# STM32L.net
KiCad netlist of a schematic drawn in Altium Designer
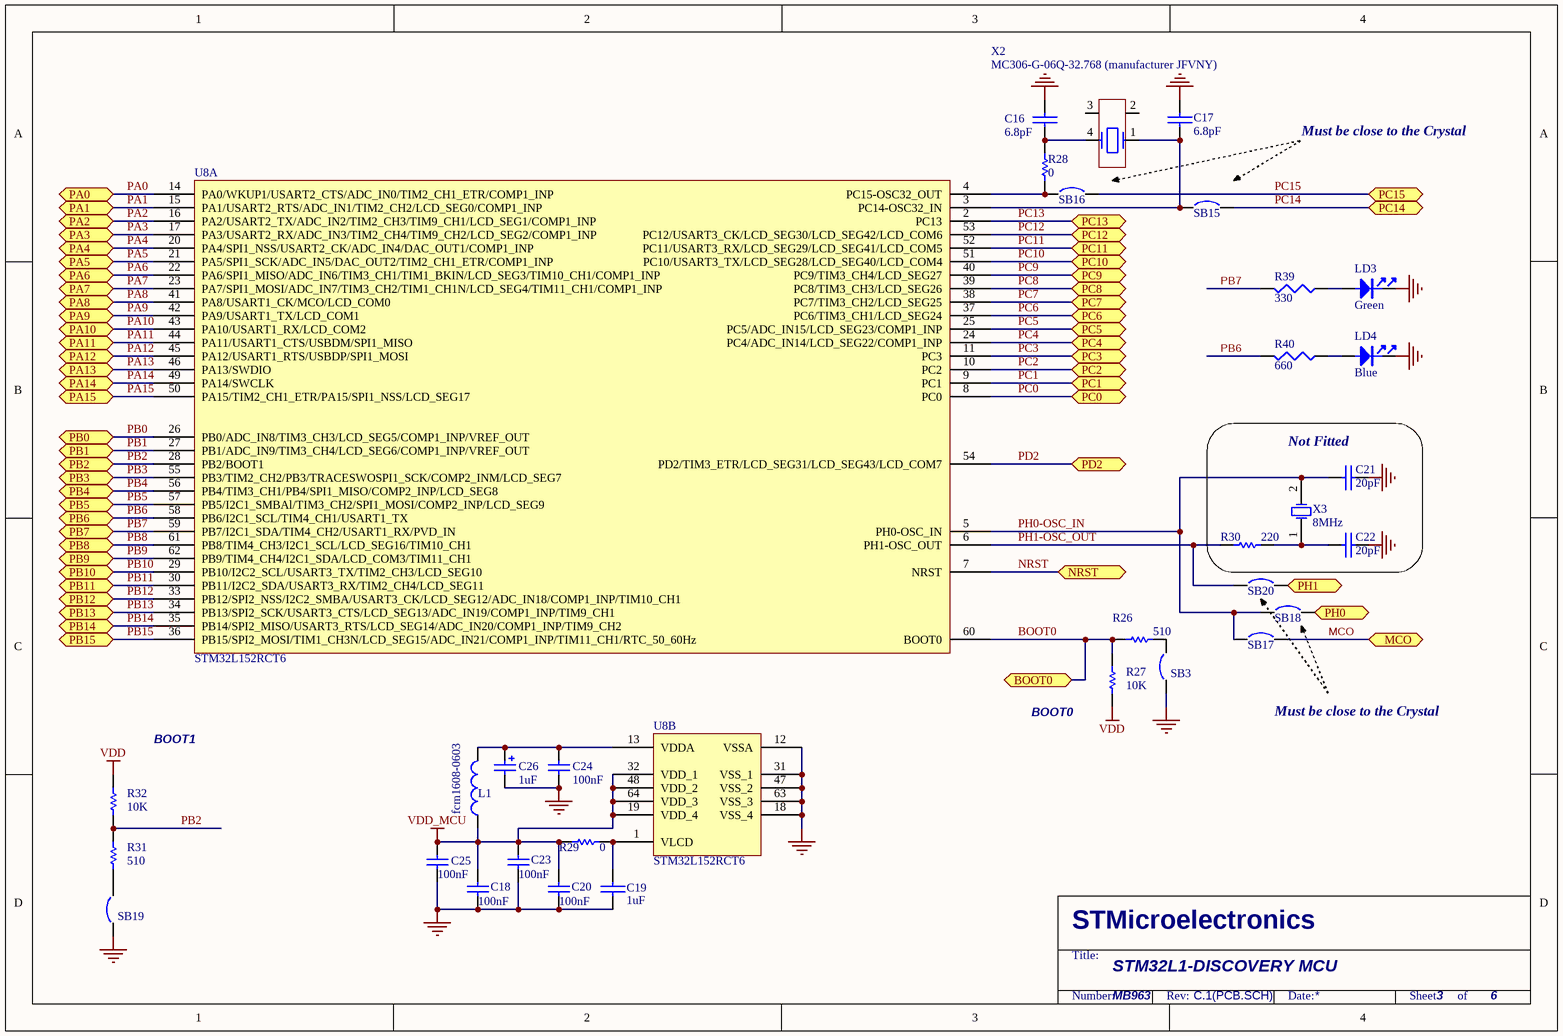
[diagram p0: STM32L.SchDoc]

(export (version "E")
  (design (tool "Eeschema 10.0.6"))
  (components
    (comp (ref "C16")
      (value "6.8pF")
      (footprint "0603C")
      (description "Capacitor")
      (libsource (lib "*") (part "CAP"))
    )
    (comp (ref "C17")
      (value "6.8pF")
      (footprint "0603C")
      (description "Capacitor")
      (libsource (lib "*") (part "CAP"))
    )
    (comp (ref "C18")
      (value "100nF")
      (footprint "0402C")
      (description "Capacitor")
      (fields (field (name "PUBLISHER") "Altium Limited"))
      (libsource (lib "MB915_1") (part "Cap"))
    )
    (comp (ref "C19")
      (value "1uF")
      (footprint "0603C")
      (description "Capacitor")
      (libsource (lib "") (part "CAP_1"))
    )
    (comp (ref "C20")
      (value "100nF")
      (footprint "0402C")
      (description "Capacitor")
      (fields (field (name "PUBLISHER") "Altium Limited"))
      (libsource (lib "MB915_1") (part "Cap"))
    )
    (comp (ref "C21")
      (value "20pF")
      (footprint "0603C")
      (description "Capacitor")
      (libsource (lib "") (part "CAP_1"))
    )
    (comp (ref "C22")
      (value "20pF")
      (footprint "0603C")
      (description "Capacitor")
      (libsource (lib "") (part "CAP_1"))
    )
    (comp (ref "C23")
      (value "100nF")
      (footprint "0402C")
      (description "Capacitor")
      (fields (field (name "PUBLISHER") "Altium Limited"))
      (libsource (lib "MB915_1") (part "Cap"))
    )
    (comp (ref "C24")
      (value "100nF")
      (footprint "0402C")
      (description "Capacitor")
      (fields (field (name "PUBLISHER") "Altium Limited"))
      (libsource (lib "MB915_1") (part "Cap"))
    )
    (comp (ref "C25")
      (value "100nF")
      (footprint "0402C")
      (description "Capacitor")
      (fields (field (name "PUBLISHER") "Altium Limited"))
      (libsource (lib "MB915_1") (part "Cap"))
    )
    (comp (ref "C26")
      (value "1uF")
      (footprint "CASE-AA")
      (description "Polarized Capacitor (Radial)")
      (fields (field (name "PUBLISHER") "Altium Limited"))
      (libsource (lib "Miscellaneous Devices") (part "Cap Pol1"))
    )
    (comp (ref "L1")
      (value "fcm1608-0603")
      (footprint "0603L")
      (description "Inductor")
      (fields (field (name "PUBLISHER") "Altium Limited"))
      (libsource (lib "Miscellaneous Devices") (part "Inductor"))
    )
    (comp (ref "LD3") (value "Green") (footprint "0603D") (libsource (lib "MB963_1") (part "PHOTO")))
    (comp (ref "LD4") (value "Blue") (footprint "0603D") (libsource (lib "MB963_1") (part "PHOTO")))
    (comp (ref "R26")
      (value "510")
      (footprint "0603R")
      (description "Resistor")
      (fields (field (name "PUBLISHER") "Altium Limited"))
      (libsource (lib "Miscellaneous Devices") (part "Res1"))
    )
    (comp (ref "R27")
      (value "10K")
      (footprint "0402R")
      (description "Resistor")
      (fields (field (name "PUBLISHER") "Altium Limited"))
      (libsource (lib "Miscellaneous Devices") (part "res1"))
    )
    (comp (ref "R28")
      (value "0")
      (footprint "0603R")
      (description "Resistor")
      (fields (field (name "PUBLISHER") "Altium Limited"))
      (libsource (lib "Miscellaneous Devices") (part "Res1"))
    )
    (comp (ref "R29")
      (value "0")
      (footprint "0402R")
      (description "Resistor")
      (fields (field (name "PUBLISHER") "Altium Limited"))
      (libsource (lib "Miscellaneous Devices") (part "res1"))
    )
    (comp (ref "R30")
      (value "220")
      (footprint "0603R")
      (description "Resistor")
      (fields (field (name "PUBLISHER") "Altium Limited"))
      (libsource (lib "Miscellaneous Devices") (part "Res1"))
    )
    (comp (ref "R31")
      (value "510")
      (footprint "0603R")
      (description "Resistor")
      (fields (field (name "PUBLISHER") "Altium Limited"))
      (libsource (lib "Miscellaneous Devices") (part "res1"))
    )
    (comp (ref "R32")
      (value "10K")
      (footprint "0402R")
      (description "Resistor")
      (fields (field (name "PUBLISHER") "Altium Limited"))
      (libsource (lib "Miscellaneous Devices") (part "res1"))
    )
    (comp (ref "R39") (value "330") (footprint "0603R") (libsource (lib "*") (part "RES1")))
    (comp (ref "R40") (value "660") (footprint "0603R") (libsource (lib "*") (part "RES1")))
    (comp (ref "SB3")
      (value "Circuit Breaker")
      (footprint "JP2_SMD")
      (fields (field (name "PUBLISHER") "Altium Limited"))
      (libsource (lib "MB915") (part "Circuit Breaker"))
    )
    (comp (ref "SB15")
      (value "Circuit Breaker")
      (footprint "JP2_SMD")
      (fields (field (name "PUBLISHER") "Altium Limited"))
      (libsource (lib "MB915") (part "Circuit Breaker"))
    )
    (comp (ref "SB16")
      (value "Circuit Breaker")
      (footprint "JP2_SMD")
      (fields (field (name "PUBLISHER") "Altium Limited"))
      (libsource (lib "MB915") (part "Circuit Breaker"))
    )
    (comp (ref "SB17")
      (value "Circuit Breaker")
      (footprint "JP2_SMD")
      (fields (field (name "PUBLISHER") "Altium Limited"))
      (libsource (lib "MB915") (part "Circuit Breaker"))
    )
    (comp (ref "SB18")
      (value "Circuit Breaker")
      (footprint "JP2_SMD")
      (fields (field (name "PUBLISHER") "Altium Limited"))
      (libsource (lib "MB915") (part "Circuit Breaker"))
    )
    (comp (ref "SB19")
      (value "Circuit Breaker")
      (footprint "JP2_SMD")
      (fields (field (name "PUBLISHER") "Altium Limited"))
      (libsource (lib "MB915") (part "Circuit Breaker"))
    )
    (comp (ref "SB20")
      (value "Circuit Breaker")
      (footprint "JP2_SMD")
      (fields (field (name "PUBLISHER") "Altium Limited"))
      (libsource (lib "MB915") (part "Circuit Breaker"))
    )
    (comp (ref "U8")
      (value "STM32L152RCT6")
      (footprint "QFP64")
      (description "32-bit 256K MCU (SCORPIO2 Shrink)")
      (libsource (lib "MB963") (part "STM32L152RCT6"))
    )
    (comp (ref "X2")
      (value "MC306-G-06Q-32.768 (manufacturer JFVNY)")
      (footprint "MC306-CRYSTAL")
      (libsource (lib "*") (part "MC306"))
    )
    (comp (ref "X3")
      (value "8MHz")
      (footprint "XTAL1")
      (description "Crystal Oscillator")
      (fields (field (name "PUBLISHER") "Altium Limited"))
      (libsource (lib "MB963_1") (part "XTAL"))
    )
  )
  (nets
    (net (code "1") (name "/BOOT0") (class "Default")
      (node (ref "R26") (pin "2") (pinfunction "2_2") (pintype "passive"))
      (node (ref "R27") (pin "1") (pinfunction "1_1") (pintype "passive"))
      (node (ref "U8") (pin "60") (pinfunction "BOOT0_60") (pintype "passive"))
    )
    (net (code "2") (name "/MCO") (class "Default")
      (node (ref "SB17") (pin "2") (pinfunction "2_2") (pintype "passive"))
    )
    (net (code "3") (name "/NRST") (class "Default")
      (node (ref "U8") (pin "7") (pinfunction "NRST_7") (pintype "passive"))
    )
    (net (code "4") (name "/PA0") (class "Default")
      (node (ref "U8") (pin "14") (pinfunction "PA0/WKUP1/USART2_CTS/ADC_IN0/TIM2_CH1_ETR/COMP1_INP_14") (pintype "passive"))
    )
    (net (code "5") (name "/PA1") (class "Default")
      (node (ref "U8") (pin "15") (pinfunction "PA1/USART2_RTS/ADC_IN1/TIM2_CH2/LCD_SEG0/COMP1_INP_15") (pintype "passive"))
    )
    (net (code "6") (name "/PA2") (class "Default")
      (node (ref "U8") (pin "16") (pinfunction "PA2/USART2_TX/ADC_IN2/TIM2_CH3/TIM9_CH1/LCD_SEG1/COMP1_INP_16") (pintype "passive"))
    )
    (net (code "7") (name "/PA3") (class "Default")
      (node (ref "U8") (pin "17") (pinfunction "PA3/USART2_RX/ADC_IN3/TIM2_CH4/TIM9_CH2/LCD_SEG2/COMP1_INP_17") (pintype "passive"))
    )
    (net (code "8") (name "/PA4") (class "Default")
      (node (ref "U8") (pin "20") (pinfunction "PA4/SPI1_NSS/USART2_CK/ADC_IN4/DAC_OUT1/COMP1_INP_20") (pintype "passive"))
    )
    (net (code "9") (name "/PA5") (class "Default")
      (node (ref "U8") (pin "21") (pinfunction "PA5/SPI1_SCK/ADC_IN5/DAC_OUT2/TIM2_CH1_ETR/COMP1_INP_21") (pintype "passive"))
    )
    (net (code "10") (name "/PA6") (class "Default")
      (node (ref "U8") (pin "22") (pinfunction "PA6/SPI1_MISO/ADC_IN6/TIM3_CH1/TIM1_BKIN/LCD_SEG3/TIM10_CH1/COMP1_INP_22") (pintype "passive"))
    )
    (net (code "11") (name "/PA7") (class "Default")
      (node (ref "U8") (pin "23") (pinfunction "PA7/SPI1_MOSI/ADC_IN7/TIM3_CH2/TIM1_CH1N/LCD_SEG4/TIM11_CH1/COMP1_INP_23") (pintype "passive"))
    )
    (net (code "12") (name "/PA8") (class "Default")
      (node (ref "U8") (pin "41") (pinfunction "PA8/USART1_CK/MCO/LCD_COM0_41") (pintype "passive"))
    )
    (net (code "13") (name "/PA9") (class "Default")
      (node (ref "U8") (pin "42") (pinfunction "PA9/USART1_TX/LCD_COM1_42") (pintype "passive"))
    )
    (net (code "14") (name "/PA10") (class "Default")
      (node (ref "U8") (pin "43") (pinfunction "PA10/USART1_RX/LCD_COM2_43") (pintype "passive"))
    )
    (net (code "15") (name "/PA11") (class "Default")
      (node (ref "U8") (pin "44") (pinfunction "PA11/USART1_CTS/USBDM/SPI1_MISO_44") (pintype "passive"))
    )
    (net (code "16") (name "/PA12") (class "Default")
      (node (ref "U8") (pin "45") (pinfunction "PA12/USART1_RTS/USBDP/SPI1_MOSI_45") (pintype "passive"))
    )
    (net (code "17") (name "/PA13") (class "Default")
      (node (ref "U8") (pin "46") (pinfunction "PA13/SWDIO_46") (pintype "passive"))
    )
    (net (code "18") (name "/PA14") (class "Default")
      (node (ref "U8") (pin "49") (pinfunction "PA14/SWCLK_49") (pintype "passive"))
    )
    (net (code "19") (name "/PA15") (class "Default")
      (node (ref "U8") (pin "50") (pinfunction "PA15/TIM2_CH1_ETR/PA15/SPI1_NSS/LCD_SEG17_50") (pintype "passive"))
    )
    (net (code "20") (name "/PB0") (class "Default")
      (node (ref "U8") (pin "26") (pinfunction "PB0/ADC_IN8/TIM3_CH3/LCD_SEG5/COMP1_INP/VREF_OUT_26") (pintype "passive"))
    )
    (net (code "21") (name "/PB1") (class "Default")
      (node (ref "U8") (pin "27") (pinfunction "PB1/ADC_IN9/TIM3_CH4/LCD_SEG6/COMP1_INP/VREF_OUT_27") (pintype "passive"))
    )
    (net (code "22") (name "/PB2") (class "Default")
      (node (ref "R31") (pin "1") (pinfunction "1_1") (pintype "passive"))
      (node (ref "R32") (pin "2") (pinfunction "2_2") (pintype "passive"))
      (node (ref "U8") (pin "28") (pinfunction "PB2/BOOT1_28") (pintype "passive"))
    )
    (net (code "23") (name "/PB3") (class "Default")
      (node (ref "U8") (pin "55") (pinfunction "PB3/TIM2_CH2/PB3/TRACESWOSPI1_SCK/COMP2_INM/LCD_SEG7_55") (pintype "passive"))
    )
    (net (code "24") (name "/PB4") (class "Default")
      (node (ref "U8") (pin "56") (pinfunction "PB4/TIM3_CH1/PB4/SPI1_MISO/COMP2_INP/LCD_SEG8_56") (pintype "passive"))
    )
    (net (code "25") (name "/PB5") (class "Default")
      (node (ref "U8") (pin "57") (pinfunction "PB5/I2C1_SMBAl/TIM3_CH2/SPI1_MOSI/COMP2_INP/LCD_SEG9_57") (pintype "passive"))
    )
    (net (code "26") (name "/PB6") (class "Default")
      (node (ref "R40") (pin "2") (pinfunction "2_2") (pintype "passive"))
      (node (ref "U8") (pin "58") (pinfunction "PB6/I2C1_SCL/TIM4_CH1/USART1_TX_58") (pintype "passive"))
    )
    (net (code "27") (name "/PB7") (class "Default")
      (node (ref "R39") (pin "2") (pinfunction "2_2") (pintype "passive"))
      (node (ref "U8") (pin "59") (pinfunction "PB7/I2C1_SDA/TIM4_CH2/USART1_RX/PVD_IN_59") (pintype "passive"))
    )
    (net (code "28") (name "/PB8") (class "Default")
      (node (ref "U8") (pin "61") (pinfunction "PB8/TIM4_CH3/I2C1_SCL/LCD_SEG16/TIM10_CH1_61") (pintype "passive"))
    )
    (net (code "29") (name "/PB9") (class "Default")
      (node (ref "U8") (pin "62") (pinfunction "PB9/TIM4_CH4/I2C1_SDA/LCD_COM3/TIM11_CH1_62") (pintype "passive"))
    )
    (net (code "30") (name "/PB10") (class "Default")
      (node (ref "U8") (pin "29") (pinfunction "PB10/I2C2_SCL/USART3_TX/TIM2_CH3/LCD_SEG10_29") (pintype "passive"))
    )
    (net (code "31") (name "/PB11") (class "Default")
      (node (ref "U8") (pin "30") (pinfunction "PB11/I2C2_SDA/USART3_RX/TIM2_CH4/LCD_SEG11_30") (pintype "passive"))
    )
    (net (code "32") (name "/PB12") (class "Default")
      (node (ref "U8") (pin "33") (pinfunction "PB12/SPI2_NSS/I2C2_SMBA/USART3_CK/LCD_SEG12/ADC_IN18/COMP1_INP/TIM10_CH1_33") (pintype "passive"))
    )
    (net (code "33") (name "/PB13") (class "Default")
      (node (ref "U8") (pin "34") (pinfunction "PB13/SPI2_SCK/USART3_CTS/LCD_SEG13/ADC_IN19/COMP1_INP/TIM9_CH1_34") (pintype "passive"))
    )
    (net (code "34") (name "/PB14") (class "Default")
      (node (ref "U8") (pin "35") (pinfunction "PB14/SPI2_MISO/USART3_RTS/LCD_SEG14/ADC_IN20/COMP1_INP/TIM9_CH2_35") (pintype "passive"))
    )
    (net (code "35") (name "/PB15") (class "Default")
      (node (ref "U8") (pin "36") (pinfunction "PB15/SPI2_MOSI/TIM1_CH3N/LCD_SEG15/ADC_IN21/COMP1_INP/TIM11_CH1/RTC_50_60Hz_36") (pintype "passive"))
    )
    (net (code "36") (name "/PC0") (class "Default")
      (node (ref "U8") (pin "8") (pinfunction "PC0_8") (pintype "passive"))
    )
    (net (code "37") (name "/PC1") (class "Default")
      (node (ref "U8") (pin "9") (pinfunction "PC1_9") (pintype "passive"))
    )
    (net (code "38") (name "/PC2") (class "Default")
      (node (ref "U8") (pin "10") (pinfunction "PC2_10") (pintype "passive"))
    )
    (net (code "39") (name "/PC3") (class "Default")
      (node (ref "U8") (pin "11") (pinfunction "PC3_11") (pintype "passive"))
    )
    (net (code "40") (name "/PC4") (class "Default")
      (node (ref "U8") (pin "24") (pinfunction "PC4/ADC_IN14/LCD_SEG22/COMP1_INP_24") (pintype "passive"))
    )
    (net (code "41") (name "/PC5") (class "Default")
      (node (ref "U8") (pin "25") (pinfunction "PC5/ADC_IN15/LCD_SEG23/COMP1_INP_25") (pintype "passive"))
    )
    (net (code "42") (name "/PC6") (class "Default")
      (node (ref "U8") (pin "37") (pinfunction "PC6/TIM3_CH1/LCD_SEG24_37") (pintype "passive"))
    )
    (net (code "43") (name "/PC7") (class "Default")
      (node (ref "U8") (pin "38") (pinfunction "PC7/TIM3_CH2/LCD_SEG25_38") (pintype "passive"))
    )
    (net (code "44") (name "/PC8") (class "Default")
      (node (ref "U8") (pin "39") (pinfunction "PC8/TIM3_CH3/LCD_SEG26_39") (pintype "passive"))
    )
    (net (code "45") (name "/PC9") (class "Default")
      (node (ref "U8") (pin "40") (pinfunction "PC9/TIM3_CH4/LCD_SEG27_40") (pintype "passive"))
    )
    (net (code "46") (name "/PC10") (class "Default")
      (node (ref "U8") (pin "51") (pinfunction "PC10/USART3_TX/LCD_SEG28/LCD_SEG40/LCD_COM4_51") (pintype "passive"))
    )
    (net (code "47") (name "/PC11") (class "Default")
      (node (ref "U8") (pin "52") (pinfunction "PC11/USART3_RX/LCD_SEG29/LCD_SEG41/LCD_COM5_52") (pintype "passive"))
    )
    (net (code "48") (name "/PC12") (class "Default")
      (node (ref "U8") (pin "53") (pinfunction "PC12/USART3_CK/LCD_SEG30/LCD_SEG42/LCD_COM6_53") (pintype "passive"))
    )
    (net (code "49") (name "/PC13") (class "Default")
      (node (ref "U8") (pin "2") (pinfunction "PC13_2") (pintype "passive"))
    )
    (net (code "50") (name "/PC14") (class "Default")
      (node (ref "SB15") (pin "2") (pinfunction "2_2") (pintype "passive"))
    )
    (net (code "51") (name "/PC15") (class "Default")
      (node (ref "SB16") (pin "2") (pinfunction "2_2") (pintype "passive"))
    )
    (net (code "52") (name "/PD2") (class "Default")
      (node (ref "U8") (pin "54") (pinfunction "PD2/TIM3_ETR/LCD_SEG31/LCD_SEG43/LCD_COM7_54") (pintype "passive"))
    )
    (net (code "53") (name "/PH0") (class "Default")
      (node (ref "SB18") (pin "2") (pinfunction "2_2") (pintype "passive"))
    )
    (net (code "54") (name "/PH0-OSC_IN") (class "Default")
      (node (ref "C21") (pin "2") (pinfunction "2_2") (pintype "passive"))
      (node (ref "SB17") (pin "1") (pinfunction "1_1") (pintype "passive"))
      (node (ref "SB18") (pin "1") (pinfunction "1_1") (pintype "passive"))
      (node (ref "U8") (pin "5") (pinfunction "PH0-OSC_IN_5") (pintype "passive"))
      (node (ref "X3") (pin "2") (pinfunction "OSC2_2") (pintype "passive"))
    )
    (net (code "55") (name "/PH1") (class "Default")
      (node (ref "SB20") (pin "2") (pinfunction "2_2") (pintype "passive"))
    )
    (net (code "56") (name "/PH1-OSC_OUT") (class "Default")
      (node (ref "R30") (pin "2") (pinfunction "2_2") (pintype "passive"))
      (node (ref "SB20") (pin "1") (pinfunction "1_1") (pintype "passive"))
      (node (ref "U8") (pin "6") (pinfunction "PH1-OSC_OUT_6") (pintype "passive"))
    )
    (net (code "57") (name "GND") (class "Default")
      (node (ref "C16") (pin "2") (pinfunction "2_2") (pintype "passive"))
      (node (ref "C17") (pin "2") (pinfunction "2_2") (pintype "passive"))
      (node (ref "C18") (pin "1") (pinfunction "1_1") (pintype "passive"))
      (node (ref "C19") (pin "2") (pinfunction "2_2") (pintype "passive"))
      (node (ref "C20") (pin "1") (pinfunction "1_1") (pintype "passive"))
      (node (ref "C21") (pin "1") (pinfunction "1_1") (pintype "passive"))
      (node (ref "C22") (pin "1") (pinfunction "1_1") (pintype "passive"))
      (node (ref "C23") (pin "2") (pinfunction "2_2") (pintype "passive"))
      (node (ref "C24") (pin "1") (pinfunction "1_1") (pintype "passive"))
      (node (ref "C25") (pin "1") (pinfunction "1_1") (pintype "passive"))
      (node (ref "C26") (pin "2") (pinfunction "2_2") (pintype "passive"))
      (node (ref "LD3") (pin "2") (pintype "passive"))
      (node (ref "LD4") (pin "2") (pintype "passive"))
      (node (ref "SB19") (pin "1") (pinfunction "1_1") (pintype "passive"))
      (node (ref "SB3") (pin "1") (pinfunction "1_1") (pintype "passive"))
      (node (ref "U8") (pin "12") (pinfunction "VSSA_12") (pintype "passive"))
      (node (ref "U8") (pin "18") (pinfunction "VSS_4_18") (pintype "passive"))
      (node (ref "U8") (pin "31") (pinfunction "VSS_1_31") (pintype "passive"))
      (node (ref "U8") (pin "47") (pinfunction "VSS_2_47") (pintype "passive"))
      (node (ref "U8") (pin "63") (pinfunction "VSS_3_63") (pintype "passive"))
    )
    (net (code "58") (name "Net-(C16-Pad1)") (class "Default")
      (node (ref "C16") (pin "1") (pinfunction "1_1") (pintype "passive"))
      (node (ref "R28") (pin "1") (pinfunction "1_1") (pintype "passive"))
      (node (ref "X2") (pin "4") (pinfunction "4_4") (pintype "passive"))
    )
    (net (code "59") (name "Net-(LD3-Pad1)") (class "Default")
      (node (ref "LD3") (pin "1") (pintype "passive"))
      (node (ref "R39") (pin "1") (pinfunction "1_1") (pintype "passive"))
    )
    (net (code "60") (name "Net-(LD4-Pad1)") (class "Default")
      (node (ref "LD4") (pin "1") (pintype "passive"))
      (node (ref "R40") (pin "1") (pinfunction "1_1") (pintype "passive"))
    )
    (net (code "61") (name "Net-(R26-Pad1)") (class "Default")
      (node (ref "R26") (pin "1") (pinfunction "1_1") (pintype "passive"))
      (node (ref "SB3") (pin "2") (pinfunction "2_2") (pintype "passive"))
    )
    (net (code "62") (name "Net-(R31-Pad2)") (class "Default")
      (node (ref "R31") (pin "2") (pinfunction "2_2") (pintype "passive"))
      (node (ref "SB19") (pin "2") (pinfunction "2_2") (pintype "passive"))
    )
    (net (code "63") (name "Net-(U8A-PC14-OSC32_IN)") (class "Default")
      (node (ref "C17") (pin "1") (pinfunction "1_1") (pintype "passive"))
      (node (ref "SB15") (pin "1") (pinfunction "1_1") (pintype "passive"))
      (node (ref "U8") (pin "3") (pinfunction "PC14-OSC32_IN_3") (pintype "passive"))
      (node (ref "X2") (pin "1") (pinfunction "1_1") (pintype "passive"))
    )
    (net (code "64") (name "Net-(U8A-PC15-OSC32_OUT)") (class "Default")
      (node (ref "R28") (pin "2") (pinfunction "2_2") (pintype "passive"))
      (node (ref "SB16") (pin "1") (pinfunction "1_1") (pintype "passive"))
      (node (ref "U8") (pin "4") (pinfunction "PC15-OSC32_OUT_4") (pintype "passive"))
    )
    (net (code "65") (name "Net-(U8B-VDDA)") (class "Default")
      (node (ref "C24") (pin "2") (pinfunction "2_2") (pintype "passive"))
      (node (ref "C26") (pin "1") (pinfunction "1_1") (pintype "passive"))
      (node (ref "L1") (pin "2") (pinfunction "2_2") (pintype "passive"))
      (node (ref "U8") (pin "13") (pinfunction "VDDA_13") (pintype "passive"))
    )
    (net (code "66") (name "Net-(U8B-VLCD)") (class "Default")
      (node (ref "C19") (pin "1") (pinfunction "1_1") (pintype "passive"))
      (node (ref "R29") (pin "2") (pinfunction "2_2") (pintype "passive"))
      (node (ref "U8") (pin "1") (pinfunction "VLCD_1") (pintype "passive"))
    )
    (net (code "67") (name "Net-(X3-OSC1)") (class "Default")
      (node (ref "C22") (pin "2") (pinfunction "2_2") (pintype "passive"))
      (node (ref "R30") (pin "1") (pinfunction "1_1") (pintype "passive"))
      (node (ref "X3") (pin "1") (pinfunction "OSC1_1") (pintype "passive"))
    )
    (net (code "68") (name "VDD") (class "Default")
      (node (ref "R27") (pin "2") (pinfunction "2_2") (pintype "passive"))
      (node (ref "R32") (pin "1") (pinfunction "1_1") (pintype "passive"))
    )
    (net (code "69") (name "VDD_MCU") (class "Default")
      (node (ref "C18") (pin "2") (pinfunction "2_2") (pintype "passive"))
      (node (ref "C20") (pin "2") (pinfunction "2_2") (pintype "passive"))
      (node (ref "C23") (pin "1") (pinfunction "1_1") (pintype "passive"))
      (node (ref "C25") (pin "2") (pinfunction "2_2") (pintype "passive"))
      (node (ref "L1") (pin "1") (pinfunction "1_1") (pintype "passive"))
      (node (ref "R29") (pin "1") (pinfunction "1_1") (pintype "passive"))
      (node (ref "U8") (pin "19") (pinfunction "VDD_4_19") (pintype "passive"))
      (node (ref "U8") (pin "32") (pinfunction "VDD_1_32") (pintype "passive"))
      (node (ref "U8") (pin "48") (pinfunction "VDD_2_48") (pintype "passive"))
      (node (ref "U8") (pin "64") (pinfunction "VDD_3_64") (pintype "passive"))
    )
    (net (code "70") (name "unconnected-(X2-Pad2)") (class "Default")
      (node (ref "X2") (pin "2") (pinfunction "2_2") (pintype "passive"))
    )
    (net (code "71") (name "unconnected-(X2-Pad3)") (class "Default")
      (node (ref "X2") (pin "3") (pinfunction "3_3") (pintype "passive"))
    )
  )
)
